# LPCB218_-_MLP_INTERFACE.net
KiCad netlist of a schematic drawn in Altium Designer
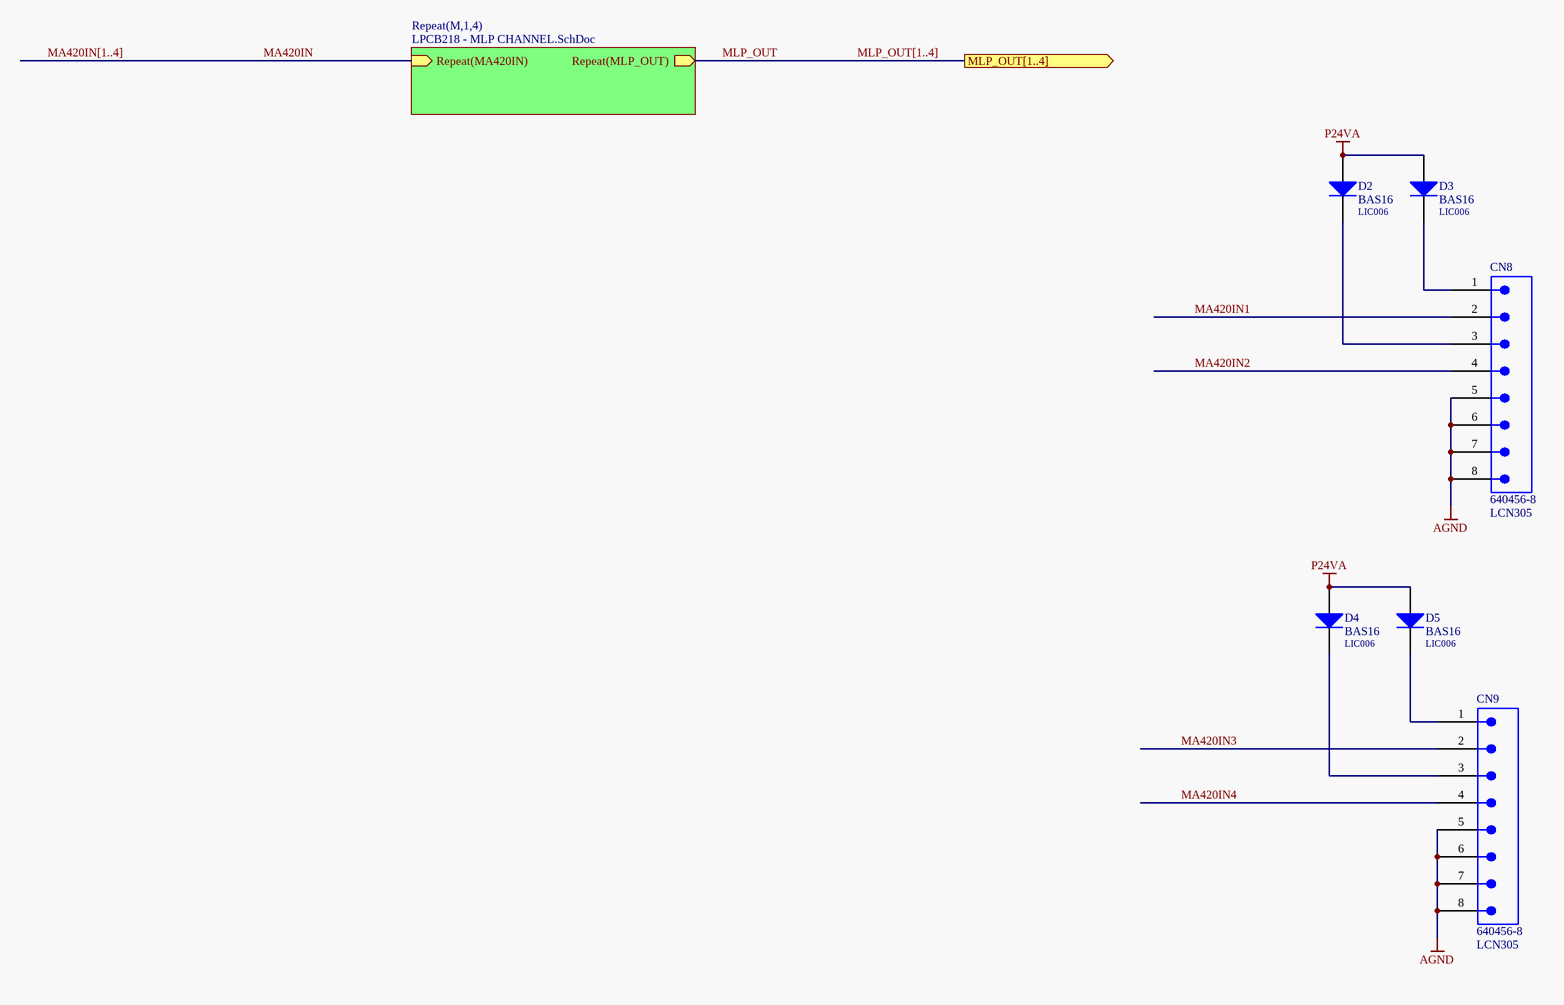
[diagram p0: LPCB218 - MLP INTERFACE.SchDoc]

(export (version "E")
  (design (tool "Eeschema 10.0.6"))
  (components
    (comp (ref "CN8")
      (value "640456-8")
      (footprint "640456-8")
      (description "Connector, Male Header, 8 Way")
      (fields (field (name "LDL_NUMBER") "LCN305"))
      (libsource (lib "LDL_Connectors") (part "640456-8"))
    )
    (comp (ref "CN9")
      (value "640456-8")
      (footprint "640456-8")
      (description "Connector, Male Header, 8 Way")
      (fields (field (name "LDL_NUMBER") "LCN305"))
      (libsource (lib "LDL_Connectors") (part "640456-8"))
    )
    (comp (ref "D2")
      (value "BAS16")
      (footprint "LFP021__SOT23")
      (description "Diode, Small Signal, 0.2A, 85V, SMD SOT-23 [LIC006]")
      (fields (field (name "LDL_NUMBER") "LIC006"))
      (libsource (lib "LDL_Semiconductors") (part "BAS16"))
    )
    (comp (ref "D3")
      (value "BAS16")
      (footprint "LFP021__SOT23")
      (description "Diode, Small Signal, 0.2A, 85V, SMD SOT-23 [LIC006]")
      (fields (field (name "LDL_NUMBER") "LIC006"))
      (libsource (lib "LDL_Semiconductors") (part "BAS16"))
    )
    (comp (ref "D4")
      (value "BAS16")
      (footprint "LFP021__SOT23")
      (description "Diode, Small Signal, 0.2A, 85V, SMD SOT-23 [LIC006]")
      (fields (field (name "LDL_NUMBER") "LIC006"))
      (libsource (lib "LDL_Semiconductors") (part "BAS16"))
    )
    (comp (ref "D5")
      (value "BAS16")
      (footprint "LFP021__SOT23")
      (description "Diode, Small Signal, 0.2A, 85V, SMD SOT-23 [LIC006]")
      (fields (field (name "LDL_NUMBER") "LIC006"))
      (libsource (lib "LDL_Semiconductors") (part "BAS16"))
    )
  )
  (nets
    (net (code "6") (name "/MA420IN1") (class "Default")
      (node (ref "CN8") (pin "2") (pinfunction "2_2") (pintype "passive"))
    )
    (net (code "7") (name "/MA420IN2") (class "Default")
      (node (ref "CN8") (pin "4") (pinfunction "4_4") (pintype "passive"))
    )
    (net (code "8") (name "/MA420IN3") (class "Default")
      (node (ref "CN9") (pin "2") (pinfunction "2_2") (pintype "passive"))
    )
    (net (code "9") (name "/MA420IN4") (class "Default")
      (node (ref "CN9") (pin "4") (pinfunction "4_4") (pintype "passive"))
    )
    (net (code "13") (name "AGND") (class "Default")
      (node (ref "CN8") (pin "5") (pinfunction "5_5") (pintype "passive"))
      (node (ref "CN8") (pin "6") (pinfunction "6_6") (pintype "passive"))
      (node (ref "CN8") (pin "7") (pinfunction "7_7") (pintype "passive"))
      (node (ref "CN8") (pin "8") (pinfunction "8_8") (pintype "passive"))
      (node (ref "CN9") (pin "5") (pinfunction "5_5") (pintype "passive"))
      (node (ref "CN9") (pin "6") (pinfunction "6_6") (pintype "passive"))
      (node (ref "CN9") (pin "7") (pinfunction "7_7") (pintype "passive"))
      (node (ref "CN9") (pin "8") (pinfunction "8_8") (pintype "passive"))
    )
    (net (code "14") (name "Net-(D2-K)") (class "Default")
      (node (ref "CN8") (pin "3") (pinfunction "3_3") (pintype "passive"))
      (node (ref "D2") (pin "3") (pinfunction "K_3") (pintype "passive"))
    )
    (net (code "15") (name "Net-(D3-K)") (class "Default")
      (node (ref "CN8") (pin "1") (pinfunction "1_1") (pintype "passive"))
      (node (ref "D3") (pin "3") (pinfunction "K_3") (pintype "passive"))
    )
    (net (code "16") (name "Net-(D4-K)") (class "Default")
      (node (ref "CN9") (pin "3") (pinfunction "3_3") (pintype "passive"))
      (node (ref "D4") (pin "3") (pinfunction "K_3") (pintype "passive"))
    )
    (net (code "17") (name "Net-(D5-K)") (class "Default")
      (node (ref "CN9") (pin "1") (pinfunction "1_1") (pintype "passive"))
      (node (ref "D5") (pin "3") (pinfunction "K_3") (pintype "passive"))
    )
    (net (code "18") (name "P24VA") (class "Default")
      (node (ref "D2") (pin "1") (pinfunction "A_1") (pintype "passive"))
      (node (ref "D3") (pin "1") (pinfunction "A_1") (pintype "passive"))
      (node (ref "D4") (pin "1") (pinfunction "A_1") (pintype "passive"))
      (node (ref "D5") (pin "1") (pinfunction "A_1") (pintype "passive"))
    )
  )
)
